# ArduinoBoard.net
KiCad netlist of a schematic drawn in EAGLE
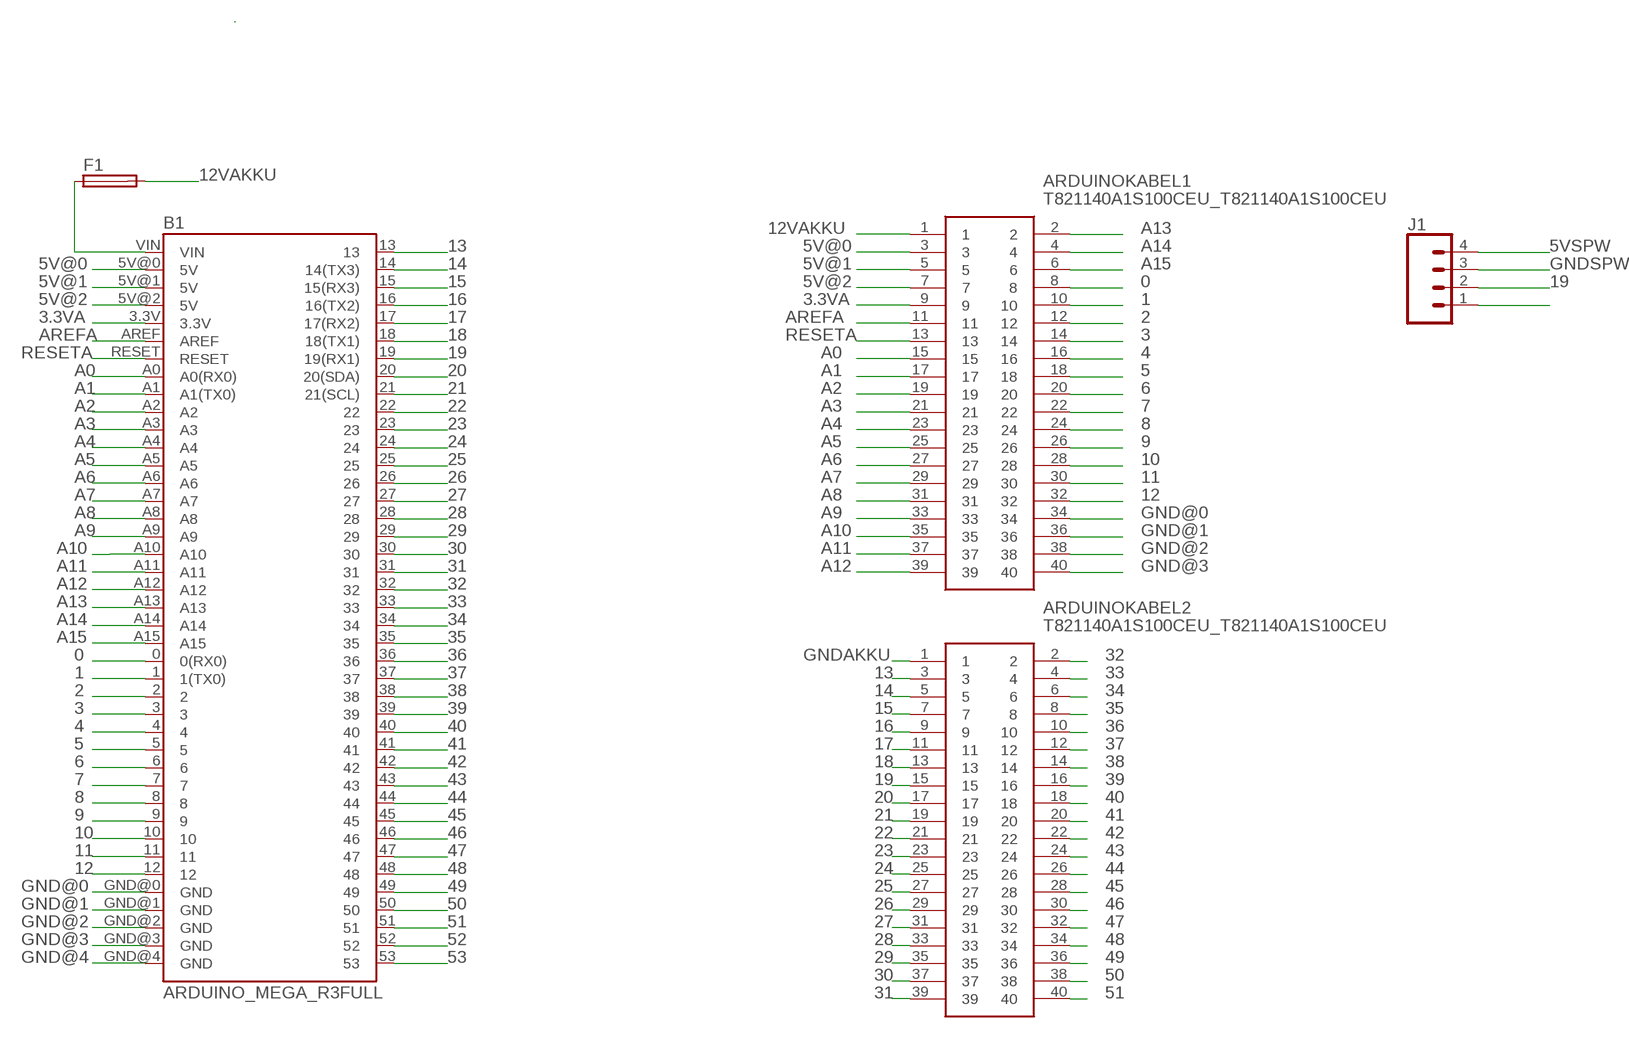
[diagram p0: schematic, sheet 1]
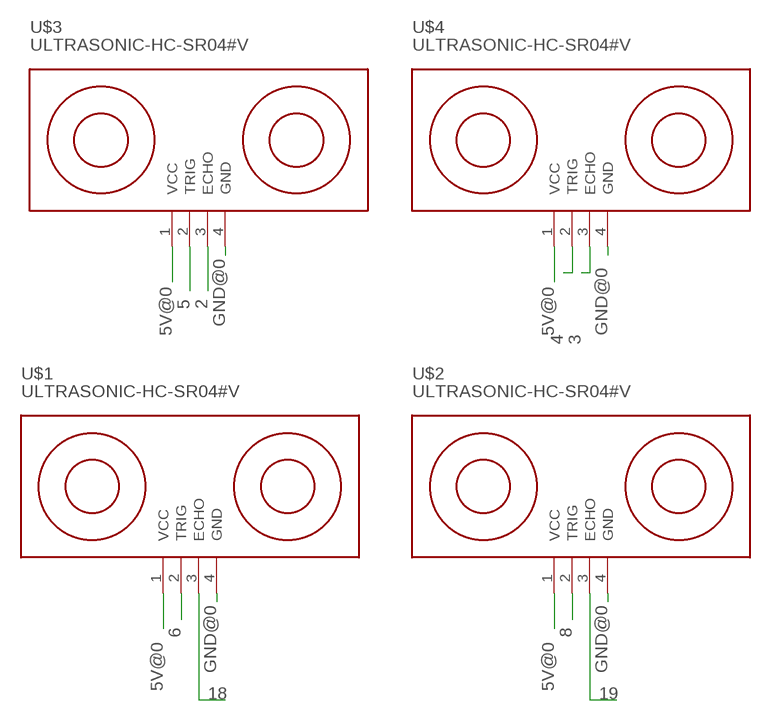
[diagram p1: schematic, sheet 2]

(export (version "E")
  (design (tool "Eeschema 10.0.6"))
  (components
    (comp (ref "ARDUINOKABEL1")
      (value "T821140A1S100CEU_T821140A1S100CEU")
      (footprint "eagle-import:T821140A1S100CEU_SHDR40W64P254X254_2X20_5842X89")
      (fields (field (name "ARROW_PART_NUMBER") "T821140A1S100CEU"))
      (libsource (lib "eagle-import") (part "T821140A1S100CEU_T821140A1S100CEU"))
    )
    (comp (ref "ARDUINOKABEL2")
      (value "T821140A1S100CEU_T821140A1S100CEU")
      (footprint "eagle-import:T821140A1S100CEU_SHDR40W64P254X254_2X20_5842X89")
      (fields (field (name "ARROW_PART_NUMBER") "T821140A1S100CEU"))
      (libsource (lib "eagle-import") (part "T821140A1S100CEU_T821140A1S100CEU"))
    )
    (comp (ref "B1")
      (value "ARDUINO_MEGA_R3FULL")
      (footprint "eagle-import:ARDUINO_MEGA")
      (libsource (lib "eagle-import") (part "ARDUINO_MEGA_R3FULL"))
    )
    (comp (ref "F1")
      (value "SH25")
      (footprint "eagle-import:SH25")
      (fields (field (name "MF") "SCHURTER") (field (name "MPN") "0031.8211"))
      (libsource (lib "eagle-import") (part "SH25"))
    )
    (comp (ref "J1")
      (value "CONN_04")
      (footprint "eagle-import:1X04")
      (libsource (lib "eagle-import") (part "CONN_04"))
    )
    (comp (ref "U$1")
      (value "ULTRASONIC-HC-SR04#V")
      (footprint "eagle-import:ULTRASONIC-HC-SR04#V")
      (libsource (lib "eagle-import") (part "ULTRASONIC-HC-SR04#V"))
    )
    (comp (ref "U$2")
      (value "ULTRASONIC-HC-SR04#V")
      (footprint "eagle-import:ULTRASONIC-HC-SR04#V")
      (libsource (lib "eagle-import") (part "ULTRASONIC-HC-SR04#V"))
    )
    (comp (ref "U$3")
      (value "ULTRASONIC-HC-SR04#V")
      (footprint "eagle-import:ULTRASONIC-HC-SR04#V")
      (libsource (lib "eagle-import") (part "ULTRASONIC-HC-SR04#V"))
    )
    (comp (ref "U$4")
      (value "ULTRASONIC-HC-SR04#V")
      (footprint "eagle-import:ULTRASONIC-HC-SR04#V")
      (libsource (lib "eagle-import") (part "ULTRASONIC-HC-SR04#V"))
    )
  )
  (nets
    (net (code "1") (name "0") (class "Default")
      (node (ref "ARDUINOKABEL1") (pin "8") (pinfunction "8_8") (pintype "bidirectional"))
      (node (ref "B1") (pin "0") (pinfunction "0(RX0)_0") (pintype "bidirectional"))
    )
    (net (code "2") (name "1") (class "Default")
      (node (ref "ARDUINOKABEL1") (pin "10") (pinfunction "10_10") (pintype "bidirectional"))
      (node (ref "B1") (pin "1") (pinfunction "1(TX0)_1") (pintype "bidirectional"))
    )
    (net (code "3") (name "2") (class "Default")
      (node (ref "ARDUINOKABEL1") (pin "12") (pinfunction "12_12") (pintype "bidirectional"))
      (node (ref "B1") (pin "2") (pinfunction "2_2") (pintype "bidirectional"))
      (node (ref "U$3") (pin "3") (pinfunction "ECHO_3") (pintype "output"))
    )
    (net (code "4") (name "3") (class "Default")
      (node (ref "ARDUINOKABEL1") (pin "14") (pinfunction "14_14") (pintype "bidirectional"))
      (node (ref "B1") (pin "3") (pinfunction "3_3") (pintype "bidirectional"))
      (node (ref "U$4") (pin "3") (pinfunction "ECHO_3") (pintype "output"))
    )
    (net (code "5") (name "3.3VA") (class "Default")
      (node (ref "ARDUINOKABEL1") (pin "9") (pinfunction "9_9") (pintype "bidirectional"))
      (node (ref "B1") (pin "3.3V") (pinfunction "3.3V_3.3V") (pintype "bidirectional"))
    )
    (net (code "6") (name "4") (class "Default")
      (node (ref "ARDUINOKABEL1") (pin "16") (pinfunction "16_16") (pintype "bidirectional"))
      (node (ref "B1") (pin "4") (pinfunction "4_4") (pintype "bidirectional"))
      (node (ref "U$4") (pin "2") (pinfunction "TRIG_2") (pintype "input"))
    )
    (net (code "7") (name "5") (class "Default")
      (node (ref "ARDUINOKABEL1") (pin "18") (pinfunction "18_18") (pintype "bidirectional"))
      (node (ref "B1") (pin "5") (pinfunction "5_5") (pintype "bidirectional"))
      (node (ref "U$3") (pin "2") (pinfunction "TRIG_2") (pintype "input"))
    )
    (net (code "8") (name "5V@0") (class "Default")
      (node (ref "ARDUINOKABEL1") (pin "3") (pinfunction "3_3") (pintype "bidirectional"))
      (node (ref "B1") (pin "5V@0") (pinfunction "5V_5V@0") (pintype "bidirectional"))
      (node (ref "U$1") (pin "1") (pinfunction "VCC_1") (pintype "power_in"))
      (node (ref "U$2") (pin "1") (pinfunction "VCC_1") (pintype "power_in"))
      (node (ref "U$3") (pin "1") (pinfunction "VCC_1") (pintype "power_in"))
      (node (ref "U$4") (pin "1") (pinfunction "VCC_1") (pintype "power_in"))
    )
    (net (code "9") (name "5V@1") (class "Default")
      (node (ref "ARDUINOKABEL1") (pin "5") (pinfunction "5_5") (pintype "bidirectional"))
      (node (ref "B1") (pin "5V@1") (pinfunction "5V_5V@1") (pintype "bidirectional"))
    )
    (net (code "10") (name "5V@2") (class "Default")
      (node (ref "ARDUINOKABEL1") (pin "7") (pinfunction "7_7") (pintype "bidirectional"))
      (node (ref "B1") (pin "5V@2") (pinfunction "5V_5V@2") (pintype "bidirectional"))
    )
    (net (code "11") (name "5VSPW") (class "Default")
      (node (ref "J1") (pin "4") (pinfunction "4_4") (pintype "passive"))
    )
    (net (code "12") (name "6") (class "Default")
      (node (ref "ARDUINOKABEL1") (pin "20") (pinfunction "20_20") (pintype "bidirectional"))
      (node (ref "B1") (pin "6") (pinfunction "6_6") (pintype "bidirectional"))
      (node (ref "U$1") (pin "2") (pinfunction "TRIG_2") (pintype "input"))
    )
    (net (code "13") (name "7") (class "Default")
      (node (ref "ARDUINOKABEL1") (pin "22") (pinfunction "22_22") (pintype "bidirectional"))
      (node (ref "B1") (pin "7") (pinfunction "7_7") (pintype "bidirectional"))
    )
    (net (code "14") (name "8") (class "Default")
      (node (ref "ARDUINOKABEL1") (pin "24") (pinfunction "24_24") (pintype "bidirectional"))
      (node (ref "B1") (pin "8") (pinfunction "8_8") (pintype "bidirectional"))
      (node (ref "U$2") (pin "2") (pinfunction "TRIG_2") (pintype "input"))
    )
    (net (code "15") (name "9") (class "Default")
      (node (ref "ARDUINOKABEL1") (pin "26") (pinfunction "26_26") (pintype "bidirectional"))
      (node (ref "B1") (pin "9") (pinfunction "9_9") (pintype "bidirectional"))
    )
    (net (code "16") (name "10") (class "Default")
      (node (ref "ARDUINOKABEL1") (pin "28") (pinfunction "28_28") (pintype "bidirectional"))
      (node (ref "B1") (pin "10") (pinfunction "10_10") (pintype "bidirectional"))
    )
    (net (code "17") (name "11") (class "Default")
      (node (ref "ARDUINOKABEL1") (pin "30") (pinfunction "30_30") (pintype "bidirectional"))
      (node (ref "B1") (pin "11") (pinfunction "11_11") (pintype "bidirectional"))
    )
    (net (code "18") (name "12") (class "Default")
      (node (ref "ARDUINOKABEL1") (pin "32") (pinfunction "32_32") (pintype "bidirectional"))
      (node (ref "B1") (pin "12") (pinfunction "12_12") (pintype "bidirectional"))
    )
    (net (code "19") (name "12VAKKU") (class "Default")
      (node (ref "ARDUINOKABEL1") (pin "1") (pinfunction "1_1") (pintype "bidirectional"))
      (node (ref "F1") (pin "2") (pinfunction "2_2") (pintype "passive"))
    )
    (net (code "20") (name "13") (class "Default")
      (node (ref "ARDUINOKABEL2") (pin "3") (pinfunction "3_3") (pintype "bidirectional"))
      (node (ref "B1") (pin "13") (pinfunction "13_13") (pintype "bidirectional"))
    )
    (net (code "21") (name "14") (class "Default")
      (node (ref "ARDUINOKABEL2") (pin "5") (pinfunction "5_5") (pintype "bidirectional"))
      (node (ref "B1") (pin "14") (pinfunction "14(TX3)_14") (pintype "bidirectional"))
    )
    (net (code "22") (name "15") (class "Default")
      (node (ref "ARDUINOKABEL2") (pin "7") (pinfunction "7_7") (pintype "bidirectional"))
      (node (ref "B1") (pin "15") (pinfunction "15(RX3)_15") (pintype "bidirectional"))
    )
    (net (code "23") (name "16") (class "Default")
      (node (ref "ARDUINOKABEL2") (pin "9") (pinfunction "9_9") (pintype "bidirectional"))
      (node (ref "B1") (pin "16") (pinfunction "16(TX2)_16") (pintype "bidirectional"))
    )
    (net (code "24") (name "17") (class "Default")
      (node (ref "ARDUINOKABEL2") (pin "11") (pinfunction "11_11") (pintype "bidirectional"))
      (node (ref "B1") (pin "17") (pinfunction "17(RX2)_17") (pintype "bidirectional"))
    )
    (net (code "25") (name "18") (class "Default")
      (node (ref "ARDUINOKABEL2") (pin "13") (pinfunction "13_13") (pintype "bidirectional"))
      (node (ref "B1") (pin "18") (pinfunction "18(TX1)_18") (pintype "bidirectional"))
      (node (ref "U$1") (pin "3") (pinfunction "ECHO_3") (pintype "output"))
    )
    (net (code "26") (name "19") (class "Default")
      (node (ref "ARDUINOKABEL2") (pin "15") (pinfunction "15_15") (pintype "bidirectional"))
      (node (ref "B1") (pin "19") (pinfunction "19(RX1)_19") (pintype "bidirectional"))
      (node (ref "J1") (pin "2") (pinfunction "2_2") (pintype "passive"))
      (node (ref "U$2") (pin "3") (pinfunction "ECHO_3") (pintype "output"))
    )
    (net (code "27") (name "20") (class "Default")
      (node (ref "ARDUINOKABEL2") (pin "17") (pinfunction "17_17") (pintype "bidirectional"))
      (node (ref "B1") (pin "20") (pinfunction "20(SDA)_20") (pintype "bidirectional"))
    )
    (net (code "28") (name "21") (class "Default")
      (node (ref "ARDUINOKABEL2") (pin "19") (pinfunction "19_19") (pintype "bidirectional"))
      (node (ref "B1") (pin "21") (pinfunction "21(SCL)_21") (pintype "bidirectional"))
    )
    (net (code "29") (name "22") (class "Default")
      (node (ref "ARDUINOKABEL2") (pin "21") (pinfunction "21_21") (pintype "bidirectional"))
      (node (ref "B1") (pin "22") (pinfunction "22_22") (pintype "bidirectional"))
    )
    (net (code "30") (name "23") (class "Default")
      (node (ref "ARDUINOKABEL2") (pin "23") (pinfunction "23_23") (pintype "bidirectional"))
      (node (ref "B1") (pin "23") (pinfunction "23_23") (pintype "bidirectional"))
    )
    (net (code "31") (name "24") (class "Default")
      (node (ref "ARDUINOKABEL2") (pin "25") (pinfunction "25_25") (pintype "bidirectional"))
      (node (ref "B1") (pin "24") (pinfunction "24_24") (pintype "bidirectional"))
    )
    (net (code "32") (name "25") (class "Default")
      (node (ref "ARDUINOKABEL2") (pin "27") (pinfunction "27_27") (pintype "bidirectional"))
      (node (ref "B1") (pin "25") (pinfunction "25_25") (pintype "bidirectional"))
    )
    (net (code "33") (name "26") (class "Default")
      (node (ref "ARDUINOKABEL2") (pin "29") (pinfunction "29_29") (pintype "bidirectional"))
      (node (ref "B1") (pin "26") (pinfunction "26_26") (pintype "bidirectional"))
    )
    (net (code "34") (name "27") (class "Default")
      (node (ref "ARDUINOKABEL2") (pin "31") (pinfunction "31_31") (pintype "bidirectional"))
      (node (ref "B1") (pin "27") (pinfunction "27_27") (pintype "bidirectional"))
    )
    (net (code "35") (name "28") (class "Default")
      (node (ref "ARDUINOKABEL2") (pin "33") (pinfunction "33_33") (pintype "bidirectional"))
      (node (ref "B1") (pin "28") (pinfunction "28_28") (pintype "bidirectional"))
    )
    (net (code "36") (name "29") (class "Default")
      (node (ref "ARDUINOKABEL2") (pin "35") (pinfunction "35_35") (pintype "bidirectional"))
      (node (ref "B1") (pin "29") (pinfunction "29_29") (pintype "bidirectional"))
    )
    (net (code "37") (name "30") (class "Default")
      (node (ref "ARDUINOKABEL2") (pin "37") (pinfunction "37_37") (pintype "bidirectional"))
      (node (ref "B1") (pin "30") (pinfunction "30_30") (pintype "bidirectional"))
    )
    (net (code "38") (name "31") (class "Default")
      (node (ref "ARDUINOKABEL2") (pin "39") (pinfunction "39_39") (pintype "bidirectional"))
      (node (ref "B1") (pin "31") (pinfunction "31_31") (pintype "bidirectional"))
    )
    (net (code "39") (name "32") (class "Default")
      (node (ref "ARDUINOKABEL2") (pin "2") (pinfunction "2_2") (pintype "bidirectional"))
      (node (ref "B1") (pin "32") (pinfunction "32_32") (pintype "bidirectional"))
    )
    (net (code "40") (name "33") (class "Default")
      (node (ref "ARDUINOKABEL2") (pin "4") (pinfunction "4_4") (pintype "bidirectional"))
      (node (ref "B1") (pin "33") (pinfunction "33_33") (pintype "bidirectional"))
    )
    (net (code "41") (name "34") (class "Default")
      (node (ref "ARDUINOKABEL2") (pin "6") (pinfunction "6_6") (pintype "bidirectional"))
      (node (ref "B1") (pin "34") (pinfunction "34_34") (pintype "bidirectional"))
    )
    (net (code "42") (name "35") (class "Default")
      (node (ref "ARDUINOKABEL2") (pin "8") (pinfunction "8_8") (pintype "bidirectional"))
      (node (ref "B1") (pin "35") (pinfunction "35_35") (pintype "bidirectional"))
    )
    (net (code "43") (name "36") (class "Default")
      (node (ref "ARDUINOKABEL2") (pin "10") (pinfunction "10_10") (pintype "bidirectional"))
      (node (ref "B1") (pin "36") (pinfunction "36_36") (pintype "bidirectional"))
    )
    (net (code "44") (name "37") (class "Default")
      (node (ref "ARDUINOKABEL2") (pin "12") (pinfunction "12_12") (pintype "bidirectional"))
      (node (ref "B1") (pin "37") (pinfunction "37_37") (pintype "bidirectional"))
    )
    (net (code "45") (name "38") (class "Default")
      (node (ref "ARDUINOKABEL2") (pin "14") (pinfunction "14_14") (pintype "bidirectional"))
      (node (ref "B1") (pin "38") (pinfunction "38_38") (pintype "bidirectional"))
    )
    (net (code "46") (name "39") (class "Default")
      (node (ref "ARDUINOKABEL2") (pin "16") (pinfunction "16_16") (pintype "bidirectional"))
      (node (ref "B1") (pin "39") (pinfunction "39_39") (pintype "bidirectional"))
    )
    (net (code "47") (name "40") (class "Default")
      (node (ref "ARDUINOKABEL2") (pin "18") (pinfunction "18_18") (pintype "bidirectional"))
      (node (ref "B1") (pin "40") (pinfunction "40_40") (pintype "bidirectional"))
    )
    (net (code "48") (name "41") (class "Default")
      (node (ref "ARDUINOKABEL2") (pin "20") (pinfunction "20_20") (pintype "bidirectional"))
      (node (ref "B1") (pin "41") (pinfunction "41_41") (pintype "bidirectional"))
    )
    (net (code "49") (name "42") (class "Default")
      (node (ref "ARDUINOKABEL2") (pin "22") (pinfunction "22_22") (pintype "bidirectional"))
      (node (ref "B1") (pin "42") (pinfunction "42_42") (pintype "bidirectional"))
    )
    (net (code "50") (name "43") (class "Default")
      (node (ref "ARDUINOKABEL2") (pin "24") (pinfunction "24_24") (pintype "bidirectional"))
      (node (ref "B1") (pin "43") (pinfunction "43_43") (pintype "bidirectional"))
    )
    (net (code "51") (name "44") (class "Default")
      (node (ref "ARDUINOKABEL2") (pin "26") (pinfunction "26_26") (pintype "bidirectional"))
      (node (ref "B1") (pin "44") (pinfunction "44_44") (pintype "bidirectional"))
    )
    (net (code "52") (name "45") (class "Default")
      (node (ref "ARDUINOKABEL2") (pin "28") (pinfunction "28_28") (pintype "bidirectional"))
      (node (ref "B1") (pin "45") (pinfunction "45_45") (pintype "bidirectional"))
    )
    (net (code "53") (name "46") (class "Default")
      (node (ref "ARDUINOKABEL2") (pin "30") (pinfunction "30_30") (pintype "bidirectional"))
      (node (ref "B1") (pin "46") (pinfunction "46_46") (pintype "bidirectional"))
    )
    (net (code "54") (name "47") (class "Default")
      (node (ref "ARDUINOKABEL2") (pin "32") (pinfunction "32_32") (pintype "bidirectional"))
      (node (ref "B1") (pin "47") (pinfunction "47_47") (pintype "bidirectional"))
    )
    (net (code "55") (name "48") (class "Default")
      (node (ref "ARDUINOKABEL2") (pin "34") (pinfunction "34_34") (pintype "bidirectional"))
      (node (ref "B1") (pin "48") (pinfunction "48_48") (pintype "bidirectional"))
    )
    (net (code "56") (name "49") (class "Default")
      (node (ref "ARDUINOKABEL2") (pin "36") (pinfunction "36_36") (pintype "bidirectional"))
      (node (ref "B1") (pin "49") (pinfunction "49_49") (pintype "bidirectional"))
    )
    (net (code "57") (name "50") (class "Default")
      (node (ref "ARDUINOKABEL2") (pin "38") (pinfunction "38_38") (pintype "bidirectional"))
      (node (ref "B1") (pin "50") (pinfunction "50_50") (pintype "bidirectional"))
    )
    (net (code "58") (name "51") (class "Default")
      (node (ref "ARDUINOKABEL2") (pin "40") (pinfunction "40_40") (pintype "bidirectional"))
      (node (ref "B1") (pin "51") (pinfunction "51_51") (pintype "bidirectional"))
    )
    (net (code "59") (name "52") (class "Default")
      (node (ref "B1") (pin "52") (pinfunction "52_52") (pintype "bidirectional"))
    )
    (net (code "60") (name "53") (class "Default")
      (node (ref "B1") (pin "53") (pinfunction "53_53") (pintype "bidirectional"))
    )
    (net (code "61") (name "A0") (class "Default")
      (node (ref "ARDUINOKABEL1") (pin "15") (pinfunction "15_15") (pintype "bidirectional"))
      (node (ref "B1") (pin "A0") (pinfunction "A0(RX0)_A0") (pintype "bidirectional"))
    )
    (net (code "62") (name "A1") (class "Default")
      (node (ref "ARDUINOKABEL1") (pin "17") (pinfunction "17_17") (pintype "bidirectional"))
      (node (ref "B1") (pin "A1") (pinfunction "A1(TX0)_A1") (pintype "bidirectional"))
    )
    (net (code "63") (name "A2") (class "Default")
      (node (ref "ARDUINOKABEL1") (pin "19") (pinfunction "19_19") (pintype "bidirectional"))
      (node (ref "B1") (pin "A2") (pinfunction "A2_A2") (pintype "bidirectional"))
    )
    (net (code "64") (name "A3") (class "Default")
      (node (ref "ARDUINOKABEL1") (pin "21") (pinfunction "21_21") (pintype "bidirectional"))
      (node (ref "B1") (pin "A3") (pinfunction "A3_A3") (pintype "bidirectional"))
    )
    (net (code "65") (name "A4") (class "Default")
      (node (ref "ARDUINOKABEL1") (pin "23") (pinfunction "23_23") (pintype "bidirectional"))
      (node (ref "B1") (pin "A4") (pinfunction "A4_A4") (pintype "bidirectional"))
    )
    (net (code "66") (name "A5") (class "Default")
      (node (ref "ARDUINOKABEL1") (pin "25") (pinfunction "25_25") (pintype "bidirectional"))
      (node (ref "B1") (pin "A5") (pinfunction "A5_A5") (pintype "bidirectional"))
    )
    (net (code "67") (name "A6") (class "Default")
      (node (ref "ARDUINOKABEL1") (pin "27") (pinfunction "27_27") (pintype "bidirectional"))
      (node (ref "B1") (pin "A6") (pinfunction "A6_A6") (pintype "bidirectional"))
    )
    (net (code "68") (name "A7") (class "Default")
      (node (ref "ARDUINOKABEL1") (pin "29") (pinfunction "29_29") (pintype "bidirectional"))
      (node (ref "B1") (pin "A7") (pinfunction "A7_A7") (pintype "bidirectional"))
    )
    (net (code "69") (name "A8") (class "Default")
      (node (ref "ARDUINOKABEL1") (pin "31") (pinfunction "31_31") (pintype "bidirectional"))
      (node (ref "B1") (pin "A8") (pinfunction "A8_A8") (pintype "bidirectional"))
    )
    (net (code "70") (name "A9") (class "Default")
      (node (ref "ARDUINOKABEL1") (pin "33") (pinfunction "33_33") (pintype "bidirectional"))
      (node (ref "B1") (pin "A9") (pinfunction "A9_A9") (pintype "bidirectional"))
    )
    (net (code "71") (name "A10") (class "Default")
      (node (ref "ARDUINOKABEL1") (pin "35") (pinfunction "35_35") (pintype "bidirectional"))
      (node (ref "B1") (pin "A10") (pinfunction "A10_A10") (pintype "bidirectional"))
    )
    (net (code "72") (name "A11") (class "Default")
      (node (ref "ARDUINOKABEL1") (pin "37") (pinfunction "37_37") (pintype "bidirectional"))
      (node (ref "B1") (pin "A11") (pinfunction "A11_A11") (pintype "bidirectional"))
    )
    (net (code "73") (name "A12") (class "Default")
      (node (ref "ARDUINOKABEL1") (pin "39") (pinfunction "39_39") (pintype "bidirectional"))
      (node (ref "B1") (pin "A12") (pinfunction "A12_A12") (pintype "bidirectional"))
    )
    (net (code "74") (name "A13") (class "Default")
      (node (ref "ARDUINOKABEL1") (pin "2") (pinfunction "2_2") (pintype "bidirectional"))
      (node (ref "B1") (pin "A13") (pinfunction "A13_A13") (pintype "bidirectional"))
    )
    (net (code "75") (name "A14") (class "Default")
      (node (ref "ARDUINOKABEL1") (pin "4") (pinfunction "4_4") (pintype "bidirectional"))
      (node (ref "B1") (pin "A14") (pinfunction "A14_A14") (pintype "bidirectional"))
    )
    (net (code "76") (name "A15") (class "Default")
      (node (ref "ARDUINOKABEL1") (pin "6") (pinfunction "6_6") (pintype "bidirectional"))
      (node (ref "B1") (pin "A15") (pinfunction "A15_A15") (pintype "bidirectional"))
    )
    (net (code "77") (name "AREFA") (class "Default")
      (node (ref "ARDUINOKABEL1") (pin "11") (pinfunction "11_11") (pintype "bidirectional"))
      (node (ref "B1") (pin "AREF") (pinfunction "AREF_AREF") (pintype "bidirectional"))
    )
    (net (code "78") (name "GND@0") (class "Default")
      (node (ref "ARDUINOKABEL1") (pin "34") (pinfunction "34_34") (pintype "bidirectional"))
      (node (ref "B1") (pin "GND@0") (pinfunction "GND_GND@0") (pintype "bidirectional"))
      (node (ref "U$1") (pin "4") (pinfunction "GND_4") (pintype "power_in"))
      (node (ref "U$2") (pin "4") (pinfunction "GND_4") (pintype "power_in"))
      (node (ref "U$3") (pin "4") (pinfunction "GND_4") (pintype "power_in"))
      (node (ref "U$4") (pin "4") (pinfunction "GND_4") (pintype "power_in"))
    )
    (net (code "79") (name "GND@1") (class "Default")
      (node (ref "ARDUINOKABEL1") (pin "36") (pinfunction "36_36") (pintype "bidirectional"))
      (node (ref "B1") (pin "GND@1") (pinfunction "GND_GND@1") (pintype "bidirectional"))
    )
    (net (code "80") (name "GND@2") (class "Default")
      (node (ref "ARDUINOKABEL1") (pin "38") (pinfunction "38_38") (pintype "bidirectional"))
      (node (ref "B1") (pin "GND@2") (pinfunction "GND_GND@2") (pintype "bidirectional"))
    )
    (net (code "81") (name "GND@3") (class "Default")
      (node (ref "ARDUINOKABEL1") (pin "40") (pinfunction "40_40") (pintype "bidirectional"))
      (node (ref "B1") (pin "GND@3") (pinfunction "GND_GND@3") (pintype "bidirectional"))
    )
    (net (code "82") (name "GND@4") (class "Default")
      (node (ref "B1") (pin "GND@4") (pinfunction "GND_GND@4") (pintype "bidirectional"))
    )
    (net (code "83") (name "GNDAKKU") (class "Default")
      (node (ref "ARDUINOKABEL2") (pin "1") (pinfunction "1_1") (pintype "bidirectional"))
    )
    (net (code "84") (name "GNDSPW") (class "Default")
      (node (ref "J1") (pin "3") (pinfunction "3_3") (pintype "passive"))
    )
    (net (code "85") (name "Net-(B1-PadVIN)") (class "Default")
      (node (ref "B1") (pin "VIN") (pinfunction "VIN_VIN") (pintype "bidirectional"))
      (node (ref "F1") (pin "1") (pinfunction "1_1") (pintype "passive"))
    )
    (net (code "86") (name "RESETA") (class "Default")
      (node (ref "ARDUINOKABEL1") (pin "13") (pinfunction "13_13") (pintype "bidirectional"))
      (node (ref "B1") (pin "RESET") (pinfunction "RESET_RESET") (pintype "bidirectional"))
    )
    (net (code "87") (name "unconnected-(J1-Pad1)") (class "Default")
      (node (ref "J1") (pin "1") (pinfunction "1_1") (pintype "passive"))
    )
  )
)
